# EchoLogger.net
KiCad netlist of a schematic drawn in EasyEDA Pro
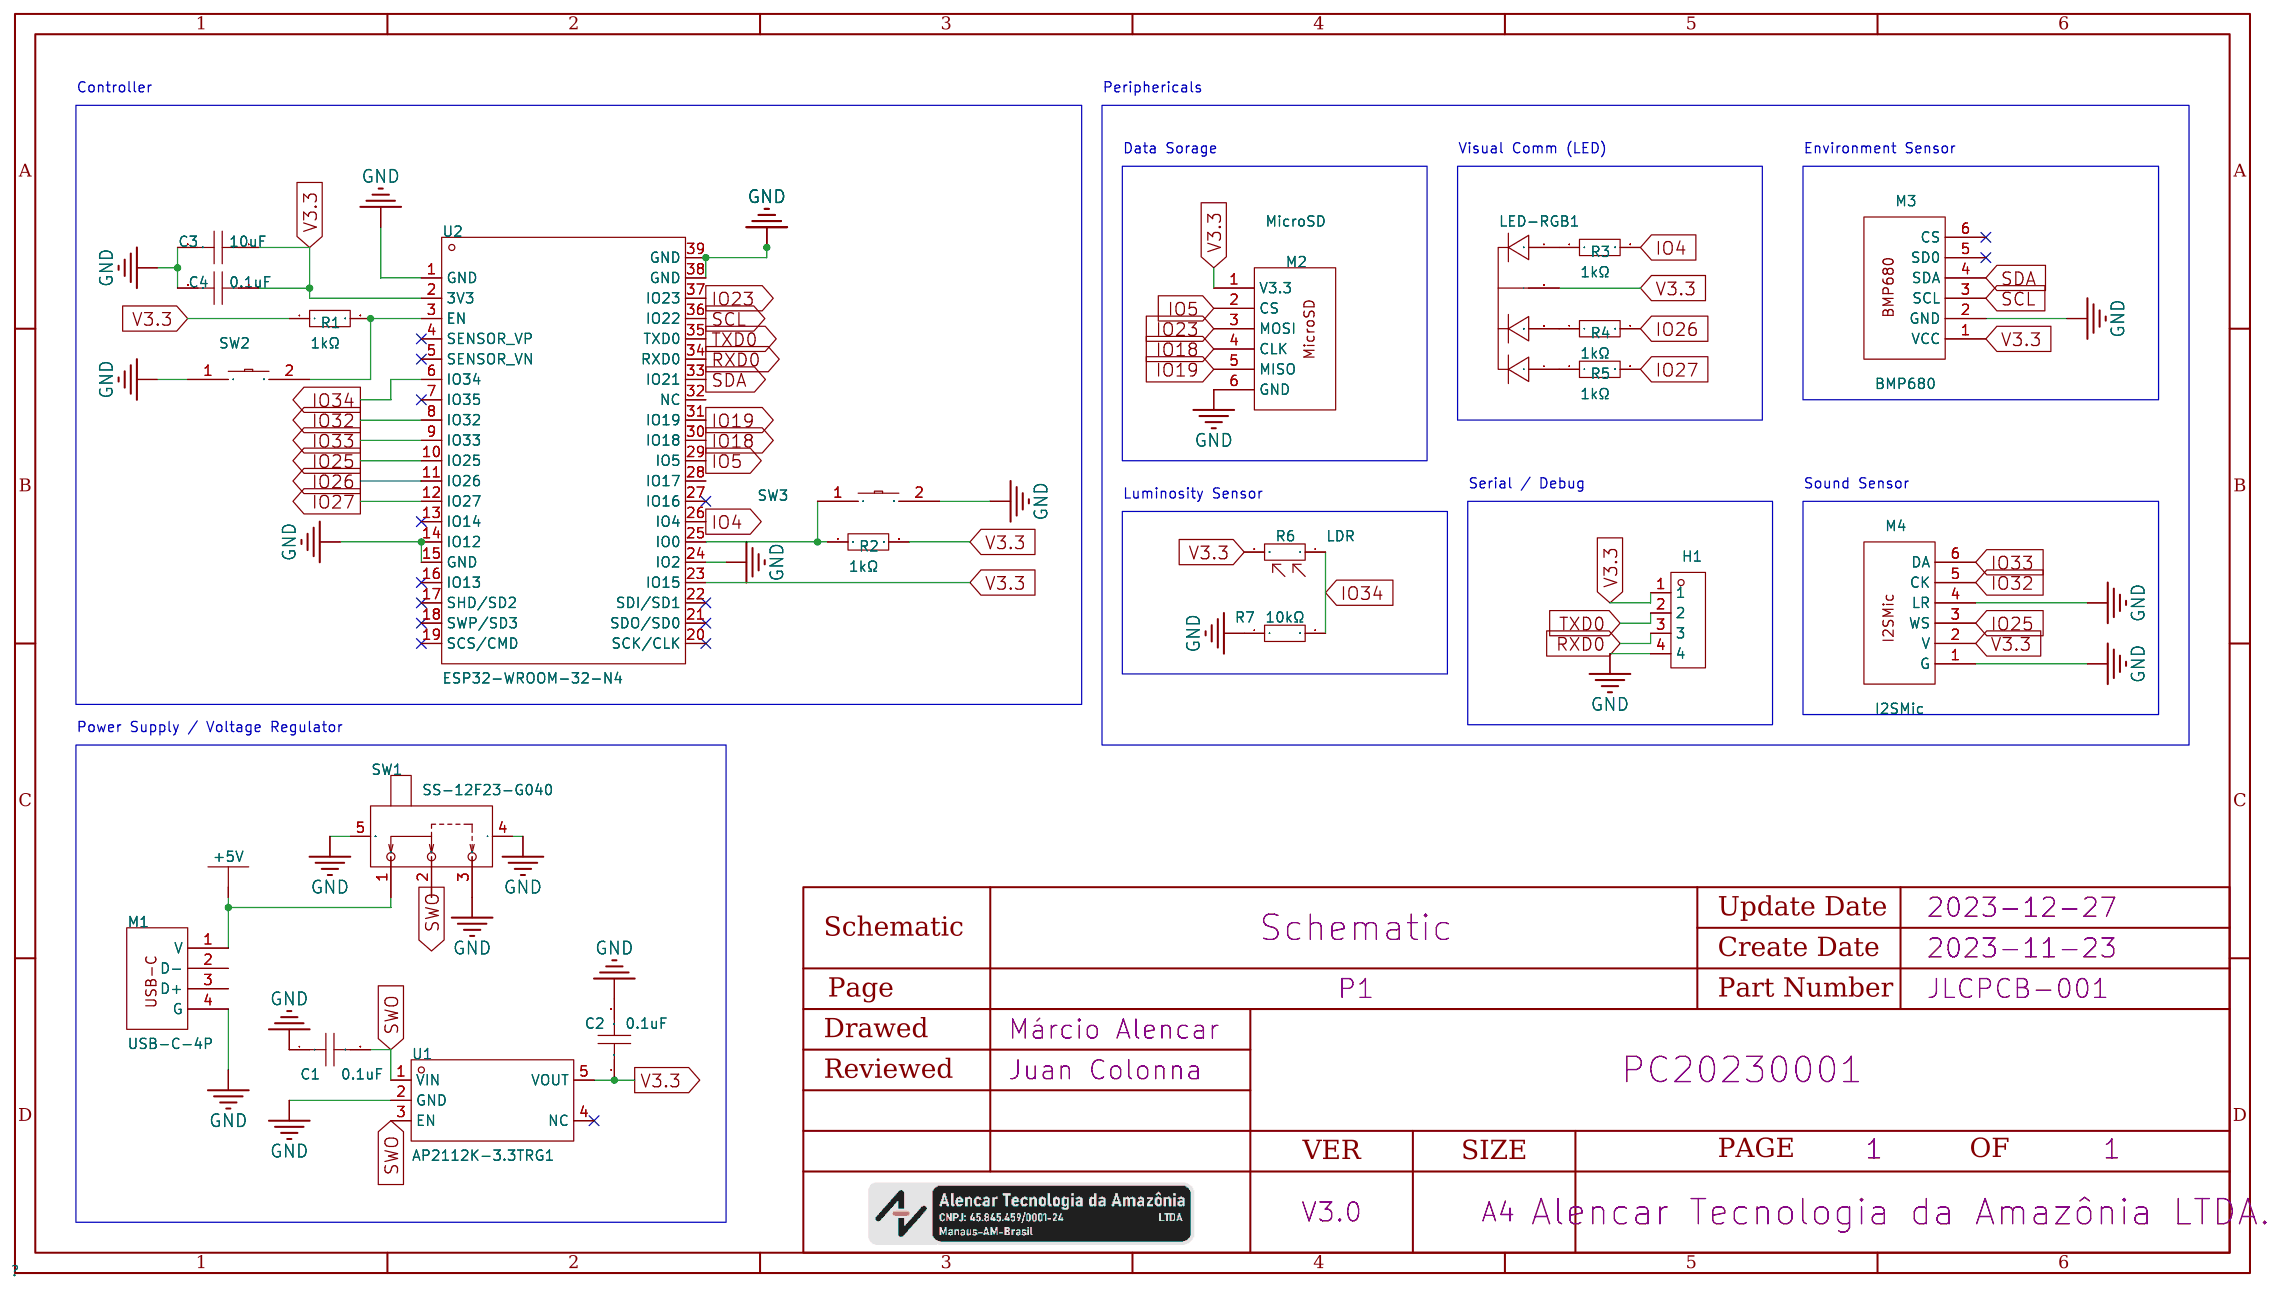
[diagram p0: schematic sheet]

(export (version "E")
  (design (tool "Eeschema 10.0.6"))
  (components
    (comp (ref "C1")
      (value "0.1uF")
      (footprint "easyedapro:C0201")
      (libsource (lib "easyedapro") (part "CAP"))
    )
    (comp (ref "C2")
      (value "0.1uF")
      (footprint "easyedapro:C0201")
      (libsource (lib "easyedapro") (part "CAP"))
    )
    (comp (ref "C3")
      (value "10uF")
      (footprint "easyedapro:C0201")
      (libsource (lib "easyedapro") (part "CAP"))
    )
    (comp (ref "C4")
      (value "0.1uF")
      (footprint "easyedapro:C0201")
      (libsource (lib "easyedapro") (part "CAP"))
    )
    (comp (ref "H1")
      (value "~")
      (footprint "easyedapro:HDR-TH_4P-P2.54-V-F")
      (libsource (lib "easyedapro") (part "2.54-1*4P母"))
    )
    (comp (ref "LED-RGB1")
      (value "LED-RGB 共阴 插件 直径5mm")
      (footprint "easyedapro:LED-TH_4P-BD5.8-P1.30")
      (libsource (lib "easyedapro") (part "LED-RGB 共阴 插件 直径5MM"))
    )
    (comp (ref "M1")
      (value "USB-C-4P")
      (footprint "easyedapro:USB-C-4P_SMD")
      (libsource (lib "easyedapro") (part "USB-C"))
    )
    (comp (ref "M2")
      (value "MicroSD")
      (footprint "easyedapro:MicroSD_SMD")
      (libsource (lib "easyedapro") (part "MicroSD"))
    )
    (comp (ref "M3")
      (value "BMP680")
      (footprint "easyedapro:BMP680_SMD")
      (libsource (lib "easyedapro") (part "BMP680"))
    )
    (comp (ref "M4")
      (value "I2SMic")
      (footprint "easyedapro:I2SMic_SMD")
      (libsource (lib "easyedapro") (part "I2SMicrophone"))
    )
    (comp (ref "R1")
      (value "1kΩ")
      (footprint "easyedapro:RES-TH_BD1.8-L3.2-P7.20-D0.4")
      (libsource (lib "easyedapro") (part "Res"))
    )
    (comp (ref "R2")
      (value "1kΩ")
      (footprint "easyedapro:RES-TH_BD1.8-L3.2-P7.20-D0.4")
      (libsource (lib "easyedapro") (part "Res"))
    )
    (comp (ref "R3")
      (value "1kΩ")
      (footprint "easyedapro:RES-TH_BD1.8-L3.2-P7.20-D0.4")
      (libsource (lib "easyedapro") (part "Res"))
    )
    (comp (ref "R4")
      (value "1kΩ")
      (footprint "easyedapro:RES-TH_BD1.8-L3.2-P7.20-D0.4")
      (libsource (lib "easyedapro") (part "Res"))
    )
    (comp (ref "R5")
      (value "1kΩ")
      (footprint "easyedapro:RES-TH_BD1.8-L3.2-P7.20-D0.4")
      (libsource (lib "easyedapro") (part "Res"))
    )
    (comp (ref "R6")
      (value "LDR")
      (footprint "easyedapro:RES-TH_L7.0-W5.9-P5.00-D0.5")
      (fields (field (name "Manufacturer") "JCHL(晶创和立)"))
      (libsource (lib "easyedapro") (part "GL7549"))
    )
    (comp (ref "R7")
      (value "10kΩ")
      (footprint "easyedapro:RES-TH_BD1.8-L3.2-P7.20-D0.4")
      (libsource (lib "easyedapro") (part "Res"))
    )
    (comp (ref "SW1")
      (value "SS-12F23-G040")
      (footprint "easyedapro:SW-TH_SS-12F23-G040")
      (fields (field (name "Manufacturer") "G-Switch(品赞)"))
      (libsource (lib "easyedapro") (part "SS-12F23-G040"))
    )
    (comp (ref "SW2")
      (value "TS-1101-C-W")
      (footprint "easyedapro:SW-SMD_L6.0-W3.3-LS8.0")
      (fields (field (name "Manufacturer") "XKB Connectivity(中国星坤)"))
      (libsource (lib "easyedapro") (part "TS-1101-C-W"))
    )
    (comp (ref "SW3")
      (value "TS-1101-C-W")
      (footprint "easyedapro:SW-SMD_L6.0-W3.3-LS8.0")
      (fields (field (name "Manufacturer") "XKB Connectivity(中国星坤)"))
      (libsource (lib "easyedapro") (part "TS-1101-C-W"))
    )
    (comp (ref "U1")
      (value "AP2112K-3.3TRG1")
      (footprint "easyedapro:SOT-25-5_L2.9-W1.6-P0.95-LS2.8-BL")
      (fields (field (name "Manufacturer") "DIODES(美台)"))
      (libsource (lib "easyedapro") (part "AP2112K-3.3TRG1"))
    )
    (comp (ref "U2")
      (value "ESP32-WROOM-32-N4")
      (footprint "easyedapro:WIFIM-SMD_ESP32-WROOM-32-N4")
      (fields (field (name "Manufacturer") "ESPRESSIF(乐鑫)"))
      (libsource (lib "easyedapro") (part "ESP32-WROOM-32"))
    )
  )
  (nets
    (net (code "1") (name "+5V") (class "Default")
      (node (ref "M1") (pin "1") (pinfunction "V_1") (pintype "input"))
      (node (ref "SW1") (pin "1") (pinfunction "1_1") (pintype "input"))
    )
    (net (code "2") (name "GND") (class "Default")
      (node (ref "C1") (pin "1") (pinfunction "1_1") (pintype "input"))
      (node (ref "C2") (pin "2") (pinfunction "2_2") (pintype "input"))
      (node (ref "C3") (pin "2") (pinfunction "2_2") (pintype "input"))
      (node (ref "C4") (pin "2") (pinfunction "2_2") (pintype "input"))
      (node (ref "H1") (pin "4") (pinfunction "4_4") (pintype "input"))
      (node (ref "M1") (pin "4") (pinfunction "G_4") (pintype "input"))
      (node (ref "M2") (pin "6") (pinfunction "GND_6") (pintype "input"))
      (node (ref "M3") (pin "2") (pinfunction "GND_2") (pintype "input"))
      (node (ref "M4") (pin "1") (pinfunction "G_1") (pintype "input"))
      (node (ref "M4") (pin "4") (pinfunction "LR_4") (pintype "input"))
      (node (ref "R7") (pin "1") (pinfunction "1_1") (pintype "input"))
      (node (ref "SW1") (pin "3") (pinfunction "3_3") (pintype "input"))
      (node (ref "SW1") (pin "4") (pinfunction "4_4") (pintype "input"))
      (node (ref "SW1") (pin "5") (pinfunction "5_5") (pintype "input"))
      (node (ref "SW2") (pin "1") (pinfunction "1_1") (pintype "input"))
      (node (ref "SW3") (pin "2") (pinfunction "2_2") (pintype "input"))
      (node (ref "U1") (pin "2") (pinfunction "GND_2") (pintype "input"))
      (node (ref "U2") (pin "1") (pinfunction "GND_1") (pintype "input"))
      (node (ref "U2") (pin "14") (pinfunction "IO12_14") (pintype "input"))
      (node (ref "U2") (pin "15") (pinfunction "GND_15") (pintype "input"))
      (node (ref "U2") (pin "24") (pinfunction "IO2_24") (pintype "input"))
      (node (ref "U2") (pin "38") (pinfunction "GND_38") (pintype "input"))
      (node (ref "U2") (pin "39") (pinfunction "GND_39") (pintype "input"))
    )
    (net (code "3") (name "IO4") (class "Default")
      (node (ref "R3") (pin "2") (pinfunction "2_2") (pintype "input"))
      (node (ref "U2") (pin "26") (pinfunction "IO4_26") (pintype "input"))
    )
    (net (code "4") (name "IO5") (class "Default")
      (node (ref "M2") (pin "2") (pinfunction "CS_2") (pintype "input"))
      (node (ref "U2") (pin "29") (pinfunction "IO5_29") (pintype "input"))
    )
    (net (code "5") (name "IO18") (class "Default")
      (node (ref "M2") (pin "4") (pinfunction "CLK_4") (pintype "input"))
      (node (ref "U2") (pin "30") (pinfunction "IO18_30") (pintype "input"))
    )
    (net (code "6") (name "IO19") (class "Default")
      (node (ref "M2") (pin "5") (pinfunction "MISO_5") (pintype "input"))
      (node (ref "U2") (pin "31") (pinfunction "IO19_31") (pintype "input"))
    )
    (net (code "7") (name "IO23") (class "Default")
      (node (ref "M2") (pin "3") (pinfunction "MOSI_3") (pintype "input"))
      (node (ref "U2") (pin "37") (pinfunction "IO23_37") (pintype "input"))
    )
    (net (code "8") (name "IO25") (class "Default")
      (node (ref "M4") (pin "3") (pinfunction "WS_3") (pintype "input"))
      (node (ref "U2") (pin "10") (pinfunction "IO25_10") (pintype "input"))
    )
    (net (code "9") (name "IO26") (class "Default")
      (node (ref "R4") (pin "2") (pinfunction "2_2") (pintype "input"))
      (node (ref "U2") (pin "11") (pinfunction "IO26_11") (pintype "input"))
    )
    (net (code "10") (name "IO27") (class "Default")
      (node (ref "R5") (pin "2") (pinfunction "2_2") (pintype "input"))
      (node (ref "U2") (pin "12") (pinfunction "IO27_12") (pintype "input"))
    )
    (net (code "11") (name "IO32") (class "Default")
      (node (ref "M4") (pin "5") (pinfunction "CK_5") (pintype "input"))
      (node (ref "U2") (pin "8") (pinfunction "IO32_8") (pintype "input"))
    )
    (net (code "12") (name "IO33") (class "Default")
      (node (ref "M4") (pin "6") (pinfunction "DA_6") (pintype "input"))
      (node (ref "U2") (pin "9") (pinfunction "IO33_9") (pintype "input"))
    )
    (net (code "13") (name "IO34") (class "Default")
      (node (ref "R6") (pin "1") (pinfunction "1_1") (pintype "input"))
      (node (ref "R7") (pin "2") (pinfunction "2_2") (pintype "input"))
      (node (ref "U2") (pin "6") (pinfunction "IO34_6") (pintype "input"))
    )
    (net (code "14") (name "Net-(LED-RGB1-Pad1)") (class "Default")
      (node (ref "LED-RGB1") (pin "1") (pinfunction "1_1") (pintype "input"))
      (node (ref "R3") (pin "1") (pinfunction "1_1") (pintype "input"))
    )
    (net (code "15") (name "Net-(LED-RGB1-Pad3)") (class "Default")
      (node (ref "LED-RGB1") (pin "3") (pinfunction "3_3") (pintype "input"))
      (node (ref "R4") (pin "1") (pinfunction "1_1") (pintype "input"))
    )
    (net (code "16") (name "Net-(LED-RGB1-Pad4)") (class "Default")
      (node (ref "LED-RGB1") (pin "4") (pinfunction "4_4") (pintype "input"))
      (node (ref "R5") (pin "1") (pinfunction "1_1") (pintype "input"))
    )
    (net (code "17") (name "Net-(U2-EN)") (class "Default")
      (node (ref "R1") (pin "2") (pinfunction "2_2") (pintype "input"))
      (node (ref "SW2") (pin "2") (pinfunction "2_2") (pintype "input"))
      (node (ref "U2") (pin "3") (pinfunction "EN_3") (pintype "input"))
    )
    (net (code "18") (name "Net-(U2-IO0)") (class "Default")
      (node (ref "R2") (pin "1") (pinfunction "1_1") (pintype "input"))
      (node (ref "SW3") (pin "1") (pinfunction "1_1") (pintype "input"))
      (node (ref "U2") (pin "25") (pinfunction "IO0_25") (pintype "input"))
    )
    (net (code "19") (name "RXD0") (class "Default")
      (node (ref "H1") (pin "3") (pinfunction "3_3") (pintype "input"))
      (node (ref "U2") (pin "34") (pinfunction "RXD0_34") (pintype "input"))
    )
    (net (code "20") (name "SCL") (class "Default")
      (node (ref "M3") (pin "3") (pinfunction "SCL_3") (pintype "input"))
      (node (ref "U2") (pin "36") (pinfunction "IO22_36") (pintype "input"))
    )
    (net (code "21") (name "SDA") (class "Default")
      (node (ref "M3") (pin "4") (pinfunction "SDA_4") (pintype "input"))
      (node (ref "U2") (pin "33") (pinfunction "IO21_33") (pintype "input"))
    )
    (net (code "22") (name "SWO") (class "Default")
      (node (ref "C1") (pin "2") (pinfunction "2_2") (pintype "input"))
      (node (ref "SW1") (pin "2") (pinfunction "2_2") (pintype "input"))
      (node (ref "U1") (pin "1") (pinfunction "VIN_1") (pintype "input"))
      (node (ref "U1") (pin "3") (pinfunction "EN_3") (pintype "input"))
    )
    (net (code "23") (name "TXD0") (class "Default")
      (node (ref "H1") (pin "2") (pinfunction "2_2") (pintype "input"))
      (node (ref "U2") (pin "35") (pinfunction "TXD0_35") (pintype "input"))
    )
    (net (code "24") (name "V3.3") (class "Default")
      (node (ref "C2") (pin "1") (pinfunction "1_1") (pintype "input"))
      (node (ref "C3") (pin "1") (pinfunction "1_1") (pintype "input"))
      (node (ref "C4") (pin "1") (pinfunction "1_1") (pintype "input"))
      (node (ref "H1") (pin "1") (pinfunction "1_1") (pintype "input"))
      (node (ref "LED-RGB1") (pin "2") (pinfunction "-_2") (pintype "input"))
      (node (ref "M2") (pin "1") (pinfunction "V3.3_1") (pintype "input"))
      (node (ref "M3") (pin "1") (pinfunction "VCC_1") (pintype "input"))
      (node (ref "M4") (pin "2") (pinfunction "V_2") (pintype "input"))
      (node (ref "R1") (pin "1") (pinfunction "1_1") (pintype "input"))
      (node (ref "R2") (pin "2") (pinfunction "2_2") (pintype "input"))
      (node (ref "R6") (pin "2") (pinfunction "2_2") (pintype "input"))
      (node (ref "U1") (pin "5") (pinfunction "VOUT_5") (pintype "input"))
      (node (ref "U2") (pin "2") (pinfunction "3V3_2") (pintype "input"))
      (node (ref "U2") (pin "23") (pinfunction "IO15_23") (pintype "input"))
    )
    (net (code "25") (name "unconnected-(M1-D+-Pad3)") (class "Default")
      (node (ref "M1") (pin "3") (pinfunction "D+_3") (pintype "input"))
    )
    (net (code "26") (name "unconnected-(M1-D--Pad2)") (class "Default")
      (node (ref "M1") (pin "2") (pinfunction "D-_2") (pintype "input"))
    )
    (net (code "27") (name "unconnected-(M3-CS-Pad6)") (class "Default")
      (node (ref "M3") (pin "6") (pinfunction "CS_6") (pintype "input+no_connect"))
    )
    (net (code "28") (name "unconnected-(M3-SD0-Pad5)") (class "Default")
      (node (ref "M3") (pin "5") (pinfunction "SD0_5") (pintype "input+no_connect"))
    )
    (net (code "29") (name "unconnected-(U1-NC-Pad4)") (class "Default")
      (node (ref "U1") (pin "4") (pinfunction "NC_4") (pintype "input+no_connect"))
    )
    (net (code "30") (name "unconnected-(U2-IO13-Pad16)") (class "Default")
      (node (ref "U2") (pin "16") (pinfunction "IO13_16") (pintype "input+no_connect"))
    )
    (net (code "31") (name "unconnected-(U2-IO14-Pad13)") (class "Default")
      (node (ref "U2") (pin "13") (pinfunction "IO14_13") (pintype "input+no_connect"))
    )
    (net (code "32") (name "unconnected-(U2-IO16-Pad27)") (class "Default")
      (node (ref "U2") (pin "27") (pinfunction "IO16_27") (pintype "input+no_connect"))
    )
    (net (code "33") (name "unconnected-(U2-IO17-Pad28)") (class "Default")
      (node (ref "U2") (pin "28") (pinfunction "IO17_28") (pintype "input"))
    )
    (net (code "34") (name "unconnected-(U2-IO35-Pad7)") (class "Default")
      (node (ref "U2") (pin "7") (pinfunction "IO35_7") (pintype "input+no_connect"))
    )
    (net (code "35") (name "unconnected-(U2-NC-Pad32)") (class "Default")
      (node (ref "U2") (pin "32") (pinfunction "NC_32") (pintype "input"))
    )
    (net (code "36") (name "unconnected-(U2-SCK{slash}CLK-Pad20)") (class "Default")
      (node (ref "U2") (pin "20") (pinfunction "SCK/CLK_20") (pintype "input+no_connect"))
    )
    (net (code "37") (name "unconnected-(U2-SCS{slash}CMD-Pad19)") (class "Default")
      (node (ref "U2") (pin "19") (pinfunction "SCS/CMD_19") (pintype "input+no_connect"))
    )
    (net (code "38") (name "unconnected-(U2-SDI{slash}SD1-Pad22)") (class "Default")
      (node (ref "U2") (pin "22") (pinfunction "SDI/SD1_22") (pintype "input+no_connect"))
    )
    (net (code "39") (name "unconnected-(U2-SDO{slash}SD0-Pad21)") (class "Default")
      (node (ref "U2") (pin "21") (pinfunction "SDO/SD0_21") (pintype "input+no_connect"))
    )
    (net (code "40") (name "unconnected-(U2-SENSOR_VN-Pad5)") (class "Default")
      (node (ref "U2") (pin "5") (pinfunction "SENSOR_VN_5") (pintype "input+no_connect"))
    )
    (net (code "41") (name "unconnected-(U2-SENSOR_VP-Pad4)") (class "Default")
      (node (ref "U2") (pin "4") (pinfunction "SENSOR_VP_4") (pintype "input+no_connect"))
    )
    (net (code "42") (name "unconnected-(U2-SHD{slash}SD2-Pad17)") (class "Default")
      (node (ref "U2") (pin "17") (pinfunction "SHD/SD2_17") (pintype "input+no_connect"))
    )
    (net (code "43") (name "unconnected-(U2-SWP{slash}SD3-Pad18)") (class "Default")
      (node (ref "U2") (pin "18") (pinfunction "SWP/SD3_18") (pintype "input+no_connect"))
    )
  )
)
